# OLM-env-sensor-REVD.net
KiCad netlist of a schematic drawn in EAGLE
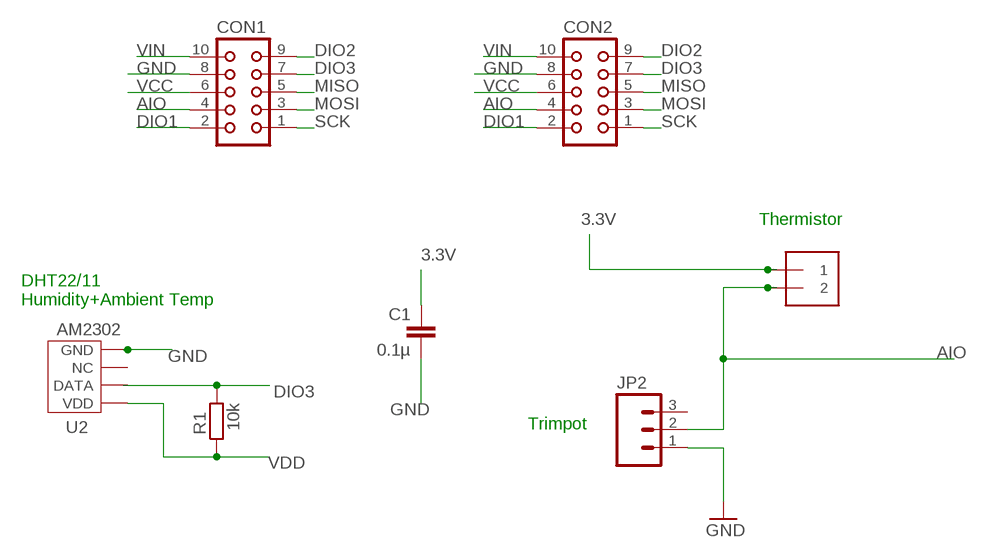
[diagram p0: schematic, sheet 1]

(export (version "E")
  (design (tool "Eeschema 10.0.6"))
  (components
    (comp (ref "C1")
      (value "0.1µ")
      (footprint "eagle-import:C025-024X044")
      (libsource (lib "eagle-import") (part "C-EU025-024X044"))
    )
    (comp (ref "CON1")
      (value "CON10L")
      (footprint "eagle-import:CON10L")
      (libsource (lib "eagle-import") (part "CON10L"))
    )
    (comp (ref "CON2")
      (value "CON10L")
      (footprint "eagle-import:CON10L")
      (libsource (lib "eagle-import") (part "CON10L"))
    )
    (comp (ref "J1")
      (value "1X2-3.5MM")
      (footprint "eagle-import:1X2-3.5MM")
      (libsource (lib "eagle-import") (part "1X2-3.5MM"))
    )
    (comp (ref "JP2")
      (value "M03PTH")
      (footprint "eagle-import:1X03")
      (libsource (lib "eagle-import") (part "M03PTH"))
    )
    (comp (ref "R1")
      (value "10k")
      (footprint "eagle-import:0204_7")
      (libsource (lib "eagle-import") (part "R-EU_0204/7"))
    )
    (comp (ref "U2")
      (value "AM2302")
      (footprint "eagle-import:AM2302")
      (libsource (lib "eagle-import") (part "AM2302"))
    )
  )
  (nets
    (net (code "1") (name "/3.3V") (class "Default")
      (node (ref "C1") (pin "1") (pinfunction "1_1") (pintype "passive"))
      (node (ref "J1") (pin "1") (pinfunction "1_1") (pintype "passive"))
    )
    (net (code "2") (name "/AIO") (class "Default")
      (node (ref "CON1") (pin "4") (pinfunction "4_4") (pintype "passive"))
      (node (ref "CON2") (pin "4") (pinfunction "4_4") (pintype "passive"))
      (node (ref "J1") (pin "2") (pinfunction "2_2") (pintype "passive"))
      (node (ref "JP2") (pin "2") (pinfunction "2_2") (pintype "passive"))
    )
    (net (code "3") (name "/DIO1") (class "Default")
      (node (ref "CON1") (pin "2") (pinfunction "2_2") (pintype "passive"))
      (node (ref "CON2") (pin "2") (pinfunction "2_2") (pintype "passive"))
    )
    (net (code "4") (name "/DIO2") (class "Default")
      (node (ref "CON1") (pin "9") (pinfunction "9_9") (pintype "passive"))
      (node (ref "CON2") (pin "9") (pinfunction "9_9") (pintype "passive"))
    )
    (net (code "5") (name "/DIO3") (class "Default")
      (node (ref "CON1") (pin "7") (pinfunction "7_7") (pintype "passive"))
      (node (ref "CON2") (pin "7") (pinfunction "7_7") (pintype "passive"))
      (node (ref "R1") (pin "2") (pinfunction "2_2") (pintype "passive"))
      (node (ref "U2") (pin "P$2") (pinfunction "DATA_P$2") (pintype "bidirectional"))
    )
    (net (code "6") (name "/MISO") (class "Default")
      (node (ref "CON1") (pin "5") (pinfunction "5_5") (pintype "passive"))
      (node (ref "CON2") (pin "5") (pinfunction "5_5") (pintype "passive"))
    )
    (net (code "7") (name "/MOSI") (class "Default")
      (node (ref "CON1") (pin "3") (pinfunction "3_3") (pintype "passive"))
      (node (ref "CON2") (pin "3") (pinfunction "3_3") (pintype "passive"))
    )
    (net (code "8") (name "/SCK") (class "Default")
      (node (ref "CON1") (pin "1") (pinfunction "1_1") (pintype "passive"))
      (node (ref "CON2") (pin "1") (pinfunction "1_1") (pintype "passive"))
    )
    (net (code "9") (name "/VCC") (class "Default")
      (node (ref "CON1") (pin "6") (pinfunction "6_6") (pintype "passive"))
      (node (ref "CON2") (pin "6") (pinfunction "6_6") (pintype "passive"))
    )
    (net (code "10") (name "/VDD") (class "Default")
      (node (ref "R1") (pin "1") (pinfunction "1_1") (pintype "passive"))
      (node (ref "U2") (pin "P$1") (pinfunction "VDD_P$1") (pintype "power_in"))
    )
    (net (code "11") (name "/VIN") (class "Default")
      (node (ref "CON1") (pin "10") (pinfunction "10_10") (pintype "passive"))
      (node (ref "CON2") (pin "10") (pinfunction "10_10") (pintype "passive"))
    )
    (net (code "12") (name "GND") (class "Default")
      (node (ref "C1") (pin "2") (pinfunction "2_2") (pintype "passive"))
      (node (ref "CON1") (pin "8") (pinfunction "8_8") (pintype "passive"))
      (node (ref "CON2") (pin "8") (pinfunction "8_8") (pintype "passive"))
      (node (ref "JP2") (pin "1") (pinfunction "1_1") (pintype "passive"))
      (node (ref "U2") (pin "P$4") (pinfunction "GND_P$4") (pintype "power_in"))
    )
    (net (code "13") (name "unconnected-(JP2-Pad3)") (class "Default")
      (node (ref "JP2") (pin "3") (pinfunction "3_3") (pintype "passive"))
    )
    (net (code "14") (name "unconnected-(U2-NC-PadP$3)") (class "Default")
      (node (ref "U2") (pin "P$3") (pinfunction "NC_P$3") (pintype "no_connect"))
    )
  )
)
